# input.net
KiCad netlist of a schematic drawn in EAGLE
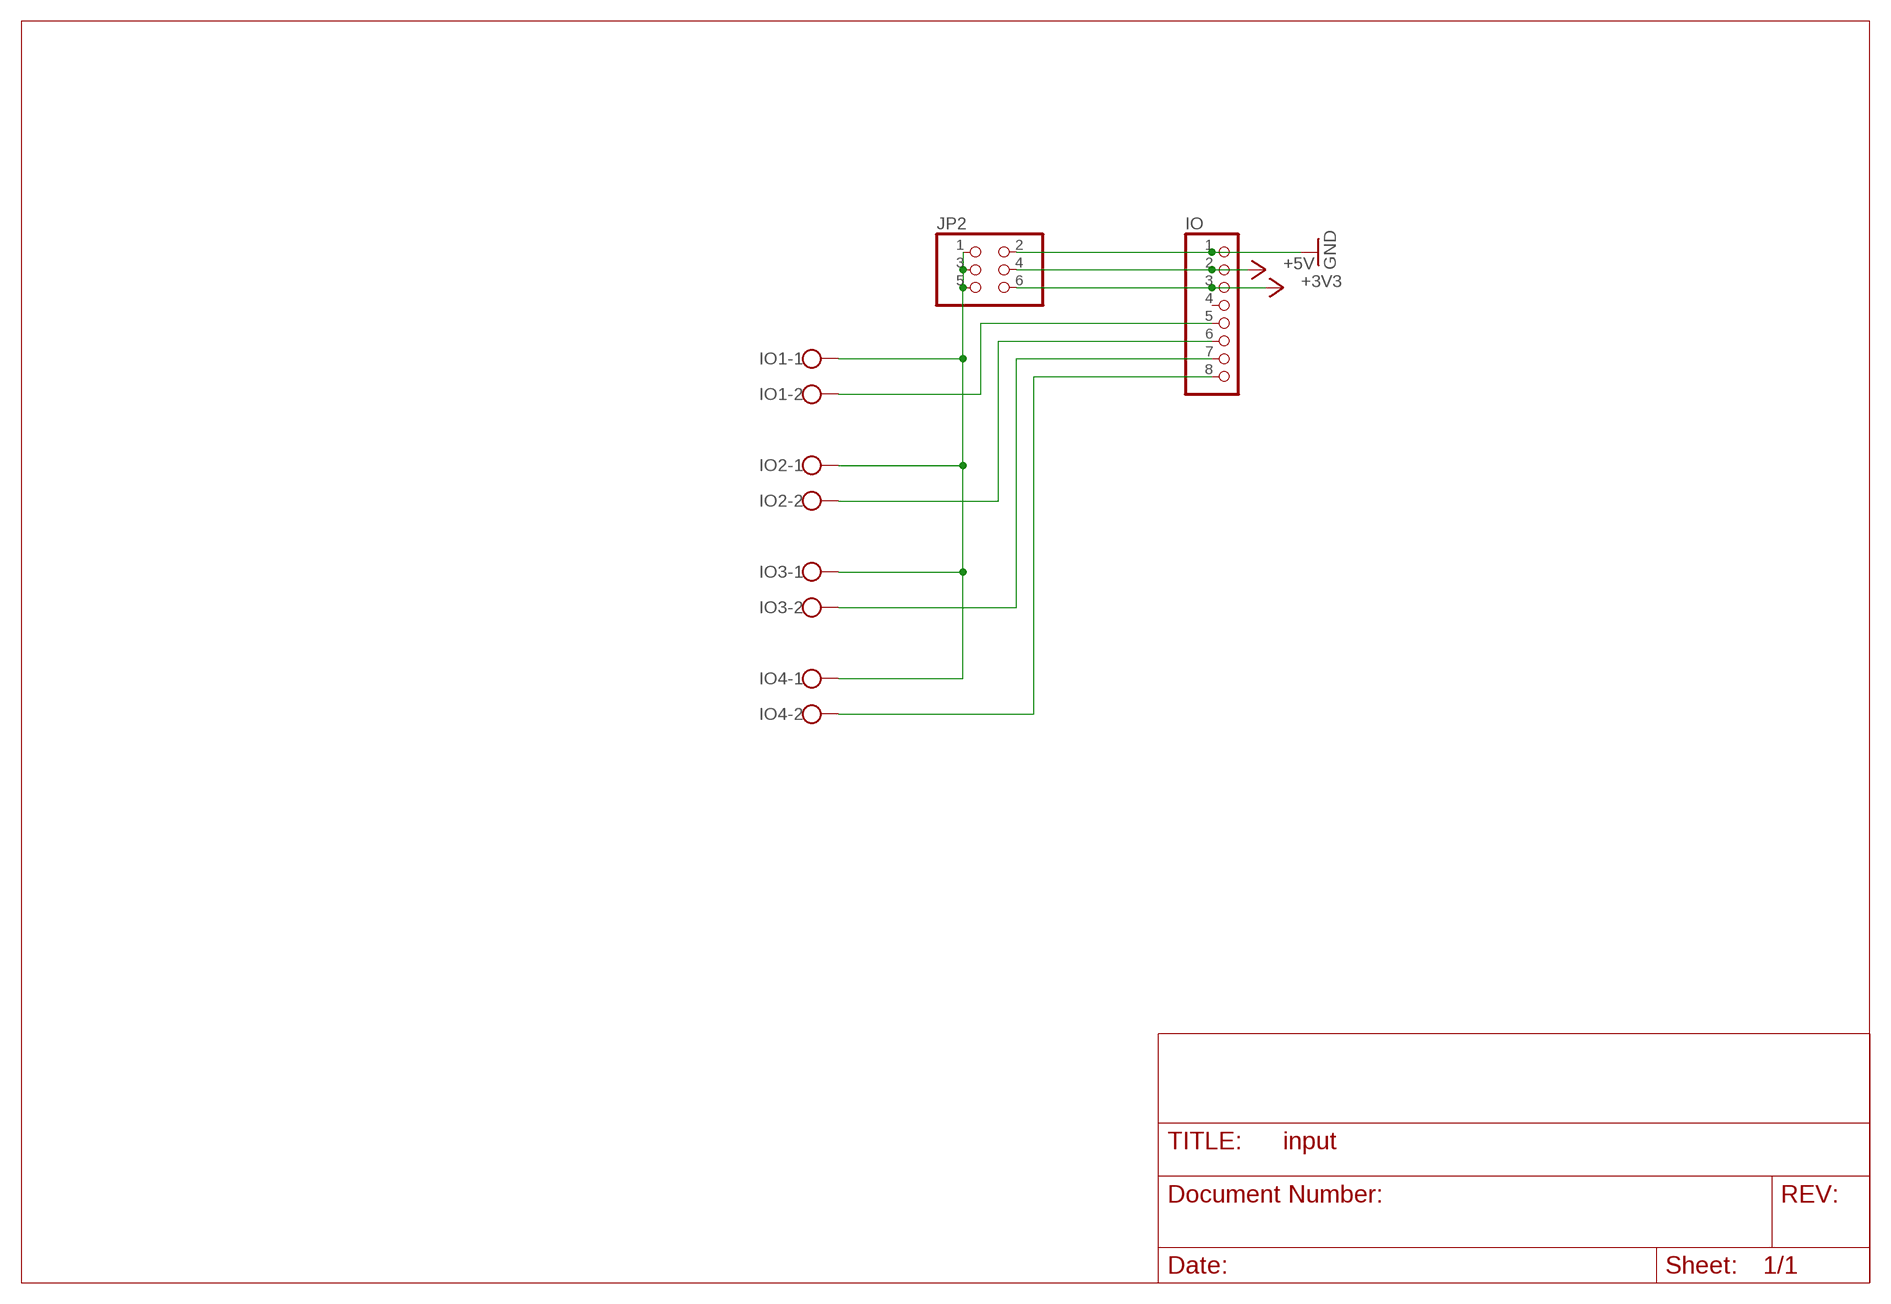
[diagram p0: schematic, sheet 1]

(export (version "E")
  (design (tool "Eeschema 10.0.6"))
  (components
    (comp (ref "IO")
      (value "PINHD-1X8")
      (footprint "eagle-import:1X08")
      (libsource (lib "eagle-import") (part "PINHD-1X8"))
    )
    (comp (ref "IO1")
      (value "W237-102")
      (footprint "eagle-import:W237-102")
      (fields (field (name "MPN") "237-102"))
      (libsource (lib "eagle-import") (part "W237-102"))
    )
    (comp (ref "IO2")
      (value "W237-102")
      (footprint "eagle-import:W237-102")
      (fields (field (name "MPN") "237-102"))
      (libsource (lib "eagle-import") (part "W237-102"))
    )
    (comp (ref "IO3")
      (value "W237-102")
      (footprint "eagle-import:W237-102")
      (fields (field (name "MPN") "237-102"))
      (libsource (lib "eagle-import") (part "W237-102"))
    )
    (comp (ref "IO4")
      (value "W237-102")
      (footprint "eagle-import:W237-102")
      (fields (field (name "MPN") "237-102"))
      (libsource (lib "eagle-import") (part "W237-102"))
    )
    (comp (ref "JP2")
      (value "PINHD-2X3")
      (footprint "eagle-import:2X03")
      (libsource (lib "eagle-import") (part "PINHD-2X3"))
    )
  )
  (nets
    (net (code "1") (name "+3V3") (class "Default")
      (node (ref "IO") (pin "3") (pinfunction "3_3") (pintype "passive"))
      (node (ref "JP2") (pin "6") (pinfunction "6_6") (pintype "passive"))
    )
    (net (code "2") (name "+5V") (class "Default")
      (node (ref "IO") (pin "2") (pinfunction "2_2") (pintype "passive"))
      (node (ref "JP2") (pin "4") (pinfunction "4_4") (pintype "passive"))
    )
    (net (code "3") (name "GND") (class "Default")
      (node (ref "IO") (pin "1") (pinfunction "1_1") (pintype "passive"))
      (node (ref "JP2") (pin "2") (pinfunction "2_2") (pintype "passive"))
    )
    (net (code "4") (name "Net-(IO1A-KL)") (class "Default")
      (node (ref "IO1") (pin "1") (pinfunction "KL_1") (pintype "passive"))
      (node (ref "IO2") (pin "1") (pinfunction "KL_1") (pintype "passive"))
      (node (ref "IO3") (pin "1") (pinfunction "KL_1") (pintype "passive"))
      (node (ref "IO4") (pin "1") (pinfunction "KL_1") (pintype "passive"))
      (node (ref "JP2") (pin "1") (pinfunction "1_1") (pintype "passive"))
      (node (ref "JP2") (pin "3") (pinfunction "3_3") (pintype "passive"))
      (node (ref "JP2") (pin "5") (pinfunction "5_5") (pintype "passive"))
    )
    (net (code "5") (name "Net-(IO1B-KL)") (class "Default")
      (node (ref "IO") (pin "5") (pinfunction "5_5") (pintype "passive"))
      (node (ref "IO1") (pin "2") (pinfunction "KL_2") (pintype "passive"))
    )
    (net (code "6") (name "Net-(IO2B-KL)") (class "Default")
      (node (ref "IO") (pin "6") (pinfunction "6_6") (pintype "passive"))
      (node (ref "IO2") (pin "2") (pinfunction "KL_2") (pintype "passive"))
    )
    (net (code "7") (name "Net-(IO3B-KL)") (class "Default")
      (node (ref "IO") (pin "7") (pinfunction "7_7") (pintype "passive"))
      (node (ref "IO3") (pin "2") (pinfunction "KL_2") (pintype "passive"))
    )
    (net (code "8") (name "Net-(IO4B-KL)") (class "Default")
      (node (ref "IO") (pin "8") (pinfunction "8_8") (pintype "passive"))
      (node (ref "IO4") (pin "2") (pinfunction "KL_2") (pintype "passive"))
    )
    (net (code "9") (name "unconnected-(IO-Pad4)") (class "Default")
      (node (ref "IO") (pin "4") (pinfunction "4_4") (pintype "passive"))
    )
  )
)
